# Statemachine_ST7735_R02.net
KiCad netlist of a schematic drawn in EAGLE
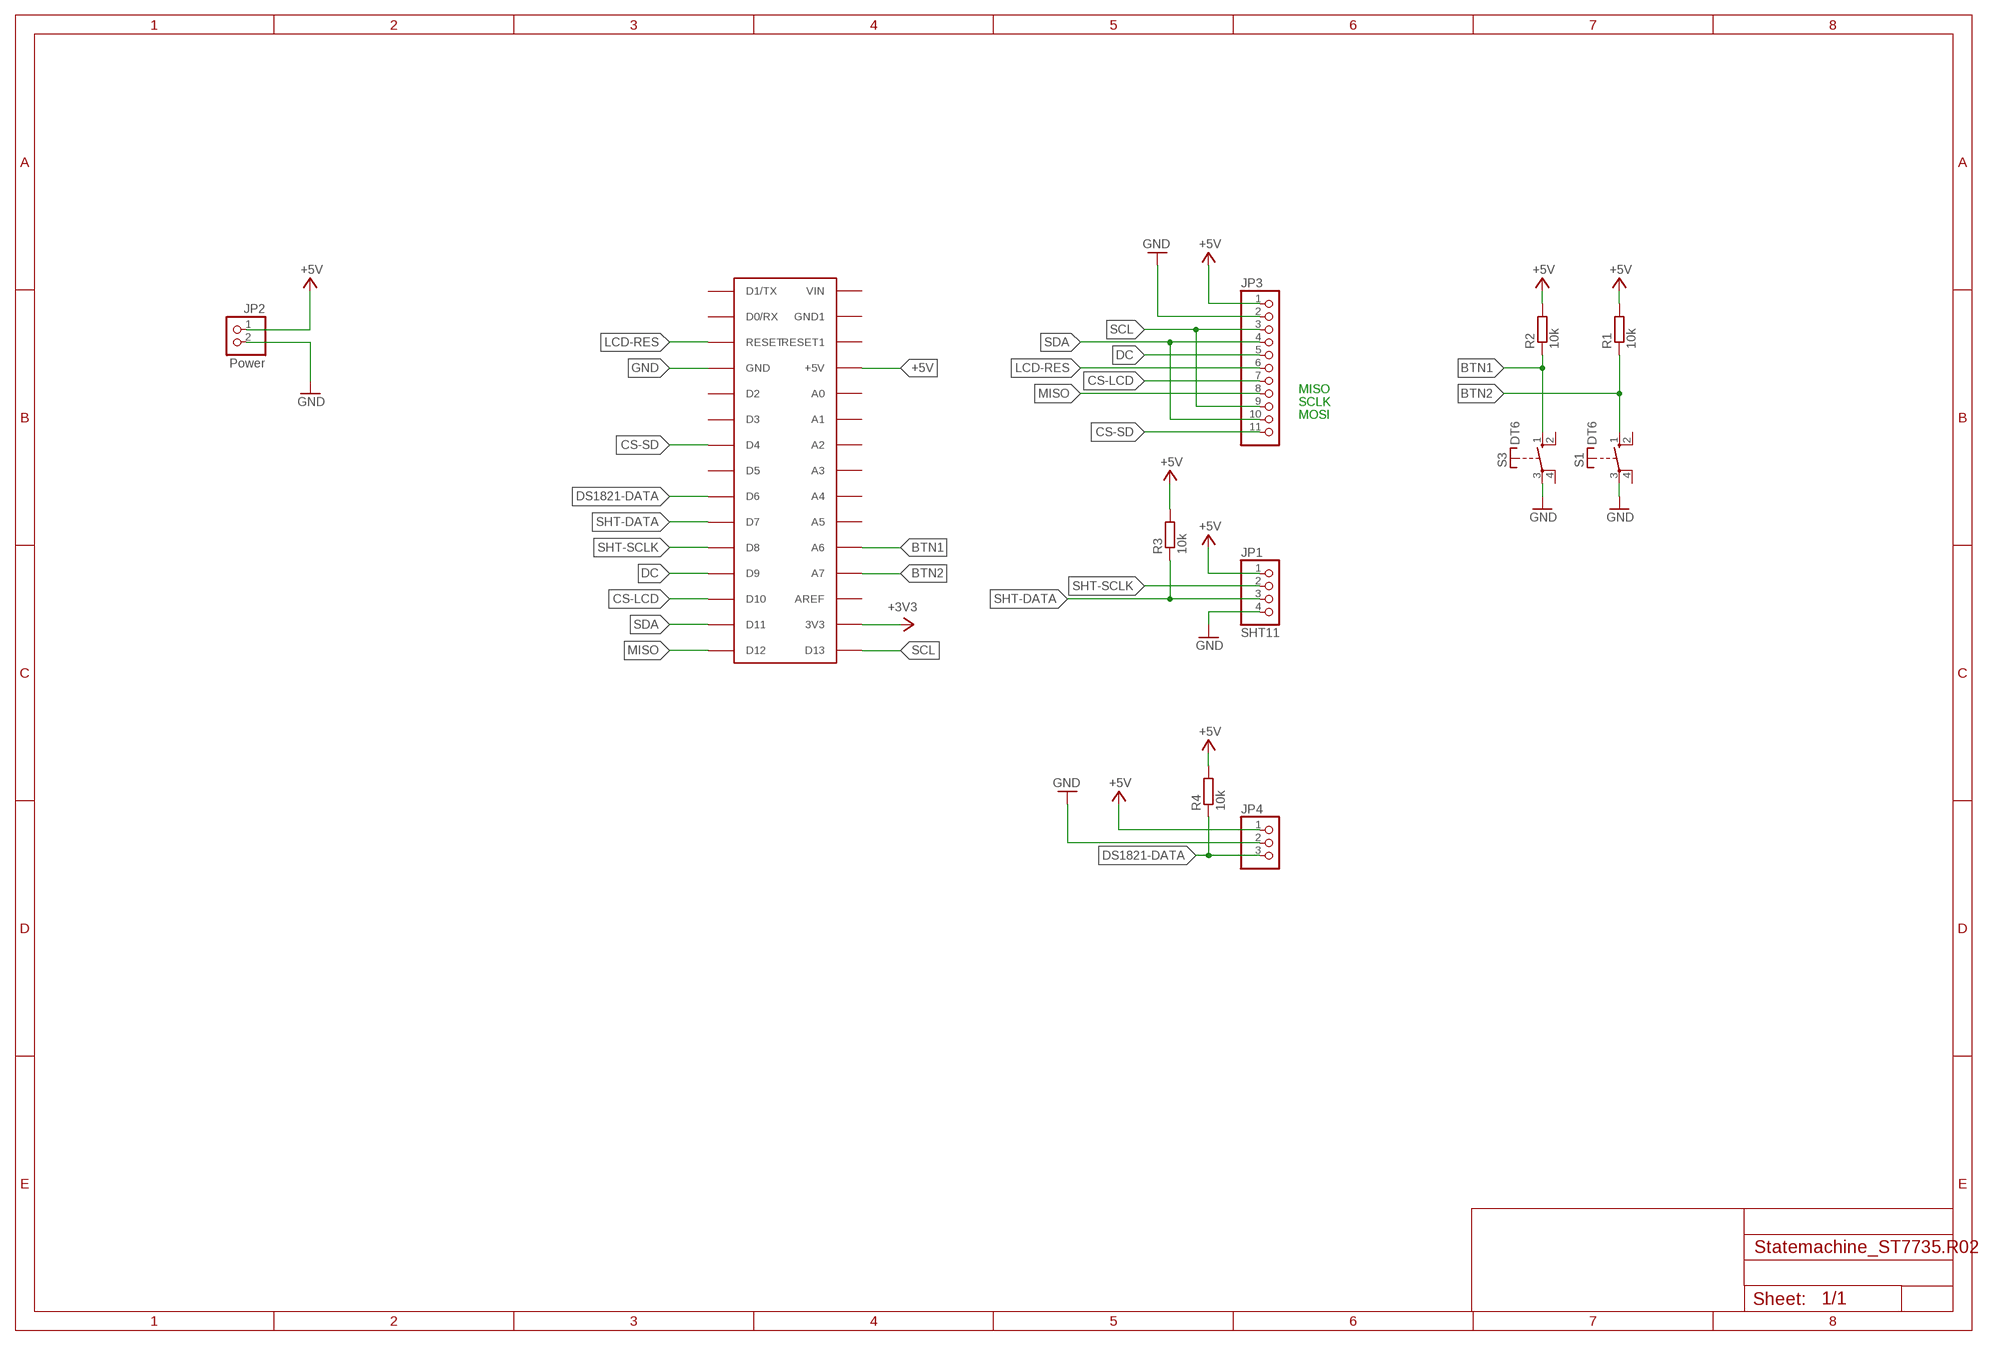
[diagram p0: schematic, sheet 1]

(export (version "E")
  (design (tool "Eeschema 10.0.6"))
  (components
    (comp (ref "JP1")
      (value "SHT11")
      (footprint "eagle-import:1X04")
      (libsource (lib "eagle-import") (part "PINHD-1X4"))
    )
    (comp (ref "JP2")
      (value "Power")
      (footprint "eagle-import:1X02")
      (libsource (lib "eagle-import") (part "PINHD-1X2"))
    )
    (comp (ref "JP3")
      (value "PINHD-1X11")
      (footprint "eagle-import:1X11")
      (libsource (lib "eagle-import") (part "PINHD-1X11"))
    )
    (comp (ref "JP4")
      (value "PINHD-1X3")
      (footprint "eagle-import:1X03")
      (libsource (lib "eagle-import") (part "PINHD-1X3"))
    )
    (comp (ref "R1")
      (value "10k")
      (footprint "eagle-import:0204_7")
      (libsource (lib "eagle-import") (part "R-EU_0204/7"))
    )
    (comp (ref "R2")
      (value "10k")
      (footprint "eagle-import:0204_7")
      (libsource (lib "eagle-import") (part "R-EU_0204/7"))
    )
    (comp (ref "R3")
      (value "10k")
      (footprint "eagle-import:0204_7")
      (libsource (lib "eagle-import") (part "R-EU_0204/7"))
    )
    (comp (ref "R4")
      (value "10k")
      (footprint "eagle-import:0204_7")
      (libsource (lib "eagle-import") (part "R-EU_0204/7"))
    )
    (comp (ref "S1")
      (value "DT6")
      (footprint "eagle-import:DT6")
      (libsource (lib "eagle-import") (part "DT6"))
    )
    (comp (ref "S3")
      (value "DT6")
      (footprint "eagle-import:DT6")
      (libsource (lib "eagle-import") (part "DT6"))
    )
    (comp (ref "U$1")
      (value "ARDUINONANO")
      (footprint "eagle-import:PDIP-32")
      (libsource (lib "eagle-import") (part "ARDUINONANO"))
    )
  )
  (nets
    (net (code "1") (name "+3V3") (class "Default")
      (node (ref "U$1") (pin "3V3") (pinfunction "3V3_3V3") (pintype "bidirectional"))
    )
    (net (code "2") (name "+5V") (class "Default")
      (node (ref "JP1") (pin "1") (pinfunction "1_1") (pintype "passive"))
      (node (ref "JP2") (pin "1") (pinfunction "1_1") (pintype "passive"))
      (node (ref "JP3") (pin "1") (pinfunction "1_1") (pintype "passive"))
      (node (ref "JP4") (pin "1") (pinfunction "1_1") (pintype "passive"))
      (node (ref "R1") (pin "2") (pinfunction "2_2") (pintype "passive"))
      (node (ref "R2") (pin "2") (pinfunction "2_2") (pintype "passive"))
      (node (ref "R3") (pin "2") (pinfunction "2_2") (pintype "passive"))
      (node (ref "R4") (pin "2") (pinfunction "2_2") (pintype "passive"))
      (node (ref "U$1") (pin "+5V") (pinfunction "+5V_+5V") (pintype "bidirectional"))
    )
    (net (code "3") (name "BTN1") (class "Default")
      (node (ref "R2") (pin "1") (pinfunction "1_1") (pintype "passive"))
      (node (ref "S3") (pin "1") (pinfunction "S_1") (pintype "passive"))
      (node (ref "U$1") (pin "A6") (pinfunction "A6_A6") (pintype "bidirectional"))
    )
    (net (code "4") (name "BTN2") (class "Default")
      (node (ref "R1") (pin "1") (pinfunction "1_1") (pintype "passive"))
      (node (ref "S1") (pin "1") (pinfunction "S_1") (pintype "passive"))
      (node (ref "U$1") (pin "A7") (pinfunction "A7_A7") (pintype "bidirectional"))
    )
    (net (code "5") (name "CS-LCD") (class "Default")
      (node (ref "JP3") (pin "7") (pinfunction "7_7") (pintype "passive"))
      (node (ref "U$1") (pin "D10") (pinfunction "D10_D10") (pintype "bidirectional"))
    )
    (net (code "6") (name "CS-SD") (class "Default")
      (node (ref "JP3") (pin "11") (pinfunction "11_11") (pintype "passive"))
      (node (ref "U$1") (pin "D4") (pinfunction "D4_D4") (pintype "bidirectional"))
    )
    (net (code "7") (name "DC") (class "Default")
      (node (ref "JP3") (pin "5") (pinfunction "5_5") (pintype "passive"))
      (node (ref "U$1") (pin "D9") (pinfunction "D9_D9") (pintype "bidirectional"))
    )
    (net (code "8") (name "DS1821-DATA") (class "Default")
      (node (ref "JP4") (pin "3") (pinfunction "3_3") (pintype "passive"))
      (node (ref "R4") (pin "1") (pinfunction "1_1") (pintype "passive"))
      (node (ref "U$1") (pin "D6") (pinfunction "D6_D6") (pintype "bidirectional"))
    )
    (net (code "9") (name "GND") (class "Default")
      (node (ref "JP1") (pin "4") (pinfunction "4_4") (pintype "passive"))
      (node (ref "JP2") (pin "2") (pinfunction "2_2") (pintype "passive"))
      (node (ref "JP3") (pin "2") (pinfunction "2_2") (pintype "passive"))
      (node (ref "JP4") (pin "2") (pinfunction "2_2") (pintype "passive"))
      (node (ref "S1") (pin "3") (pinfunction "P_3") (pintype "passive"))
      (node (ref "S3") (pin "3") (pinfunction "P_3") (pintype "passive"))
      (node (ref "U$1") (pin "GND") (pinfunction "GND_GND") (pintype "bidirectional"))
    )
    (net (code "10") (name "LCD-RES") (class "Default")
      (node (ref "JP3") (pin "6") (pinfunction "6_6") (pintype "passive"))
      (node (ref "U$1") (pin "RESET") (pinfunction "RESET_RESET") (pintype "bidirectional"))
    )
    (net (code "11") (name "MISO") (class "Default")
      (node (ref "JP3") (pin "8") (pinfunction "8_8") (pintype "passive"))
      (node (ref "U$1") (pin "D12") (pinfunction "D12_D12") (pintype "bidirectional"))
    )
    (net (code "12") (name "SCL") (class "Default")
      (node (ref "JP3") (pin "3") (pinfunction "3_3") (pintype "passive"))
      (node (ref "JP3") (pin "9") (pinfunction "9_9") (pintype "passive"))
      (node (ref "U$1") (pin "D13") (pinfunction "D13_D13") (pintype "bidirectional"))
    )
    (net (code "13") (name "SDA") (class "Default")
      (node (ref "JP3") (pin "10") (pinfunction "10_10") (pintype "passive"))
      (node (ref "JP3") (pin "4") (pinfunction "4_4") (pintype "passive"))
      (node (ref "U$1") (pin "D11") (pinfunction "D11_D11") (pintype "bidirectional"))
    )
    (net (code "14") (name "SHT-DATA") (class "Default")
      (node (ref "JP1") (pin "3") (pinfunction "3_3") (pintype "passive"))
      (node (ref "R3") (pin "1") (pinfunction "1_1") (pintype "passive"))
      (node (ref "U$1") (pin "D7") (pinfunction "D7_D7") (pintype "bidirectional"))
    )
    (net (code "15") (name "SHT-SCLK") (class "Default")
      (node (ref "JP1") (pin "2") (pinfunction "2_2") (pintype "passive"))
      (node (ref "U$1") (pin "D8") (pinfunction "D8_D8") (pintype "bidirectional"))
    )
    (net (code "16") (name "unconnected-(S1-P-Pad4)") (class "Default")
      (node (ref "S1") (pin "4") (pinfunction "P_4") (pintype "passive"))
    )
    (net (code "17") (name "unconnected-(S1-S-Pad2)") (class "Default")
      (node (ref "S1") (pin "2") (pinfunction "S_2") (pintype "passive"))
    )
    (net (code "18") (name "unconnected-(S3-P-Pad4)") (class "Default")
      (node (ref "S3") (pin "4") (pinfunction "P_4") (pintype "passive"))
    )
    (net (code "19") (name "unconnected-(S3-S-Pad2)") (class "Default")
      (node (ref "S3") (pin "2") (pinfunction "S_2") (pintype "passive"))
    )
    (net (code "20") (name "unconnected-(U$1-PadA0)") (class "Default")
      (node (ref "U$1") (pin "A0") (pinfunction "A0_A0") (pintype "bidirectional"))
    )
    (net (code "21") (name "unconnected-(U$1-PadA1)") (class "Default")
      (node (ref "U$1") (pin "A1") (pinfunction "A1_A1") (pintype "bidirectional"))
    )
    (net (code "22") (name "unconnected-(U$1-PadA2)") (class "Default")
      (node (ref "U$1") (pin "A2") (pinfunction "A2_A2") (pintype "bidirectional"))
    )
    (net (code "23") (name "unconnected-(U$1-PadA3)") (class "Default")
      (node (ref "U$1") (pin "A3") (pinfunction "A3_A3") (pintype "bidirectional"))
    )
    (net (code "24") (name "unconnected-(U$1-PadA4)") (class "Default")
      (node (ref "U$1") (pin "A4") (pinfunction "A4_A4") (pintype "bidirectional"))
    )
    (net (code "25") (name "unconnected-(U$1-PadA5)") (class "Default")
      (node (ref "U$1") (pin "A5") (pinfunction "A5_A5") (pintype "bidirectional"))
    )
    (net (code "26") (name "unconnected-(U$1-PadAREF)") (class "Default")
      (node (ref "U$1") (pin "AREF") (pinfunction "AREF_AREF") (pintype "bidirectional"))
    )
    (net (code "27") (name "unconnected-(U$1-PadD0{slash}RX)") (class "Default")
      (node (ref "U$1") (pin "D0/RX") (pinfunction "D0/RX_D0/RX") (pintype "bidirectional"))
    )
    (net (code "28") (name "unconnected-(U$1-PadD1{slash}TX)") (class "Default")
      (node (ref "U$1") (pin "D1/TX") (pinfunction "D1/TX_D1/TX") (pintype "bidirectional"))
    )
    (net (code "29") (name "unconnected-(U$1-PadD2)") (class "Default")
      (node (ref "U$1") (pin "D2") (pinfunction "D2_D2") (pintype "bidirectional"))
    )
    (net (code "30") (name "unconnected-(U$1-PadD3)") (class "Default")
      (node (ref "U$1") (pin "D3") (pinfunction "D3_D3") (pintype "bidirectional"))
    )
    (net (code "31") (name "unconnected-(U$1-PadD5)") (class "Default")
      (node (ref "U$1") (pin "D5") (pinfunction "D5_D5") (pintype "bidirectional"))
    )
    (net (code "32") (name "unconnected-(U$1-PadGND1)") (class "Default")
      (node (ref "U$1") (pin "GND1") (pinfunction "GND1_GND1") (pintype "bidirectional"))
    )
    (net (code "33") (name "unconnected-(U$1-PadRESET1)") (class "Default")
      (node (ref "U$1") (pin "RESET1") (pinfunction "RESET1_RESET1") (pintype "bidirectional"))
    )
    (net (code "34") (name "unconnected-(U$1-PadVIN)") (class "Default")
      (node (ref "U$1") (pin "VIN") (pinfunction "VIN_VIN") (pintype "bidirectional"))
    )
  )
)
